# Banks_1_2.net
KiCad netlist of a schematic drawn in Altium Designer
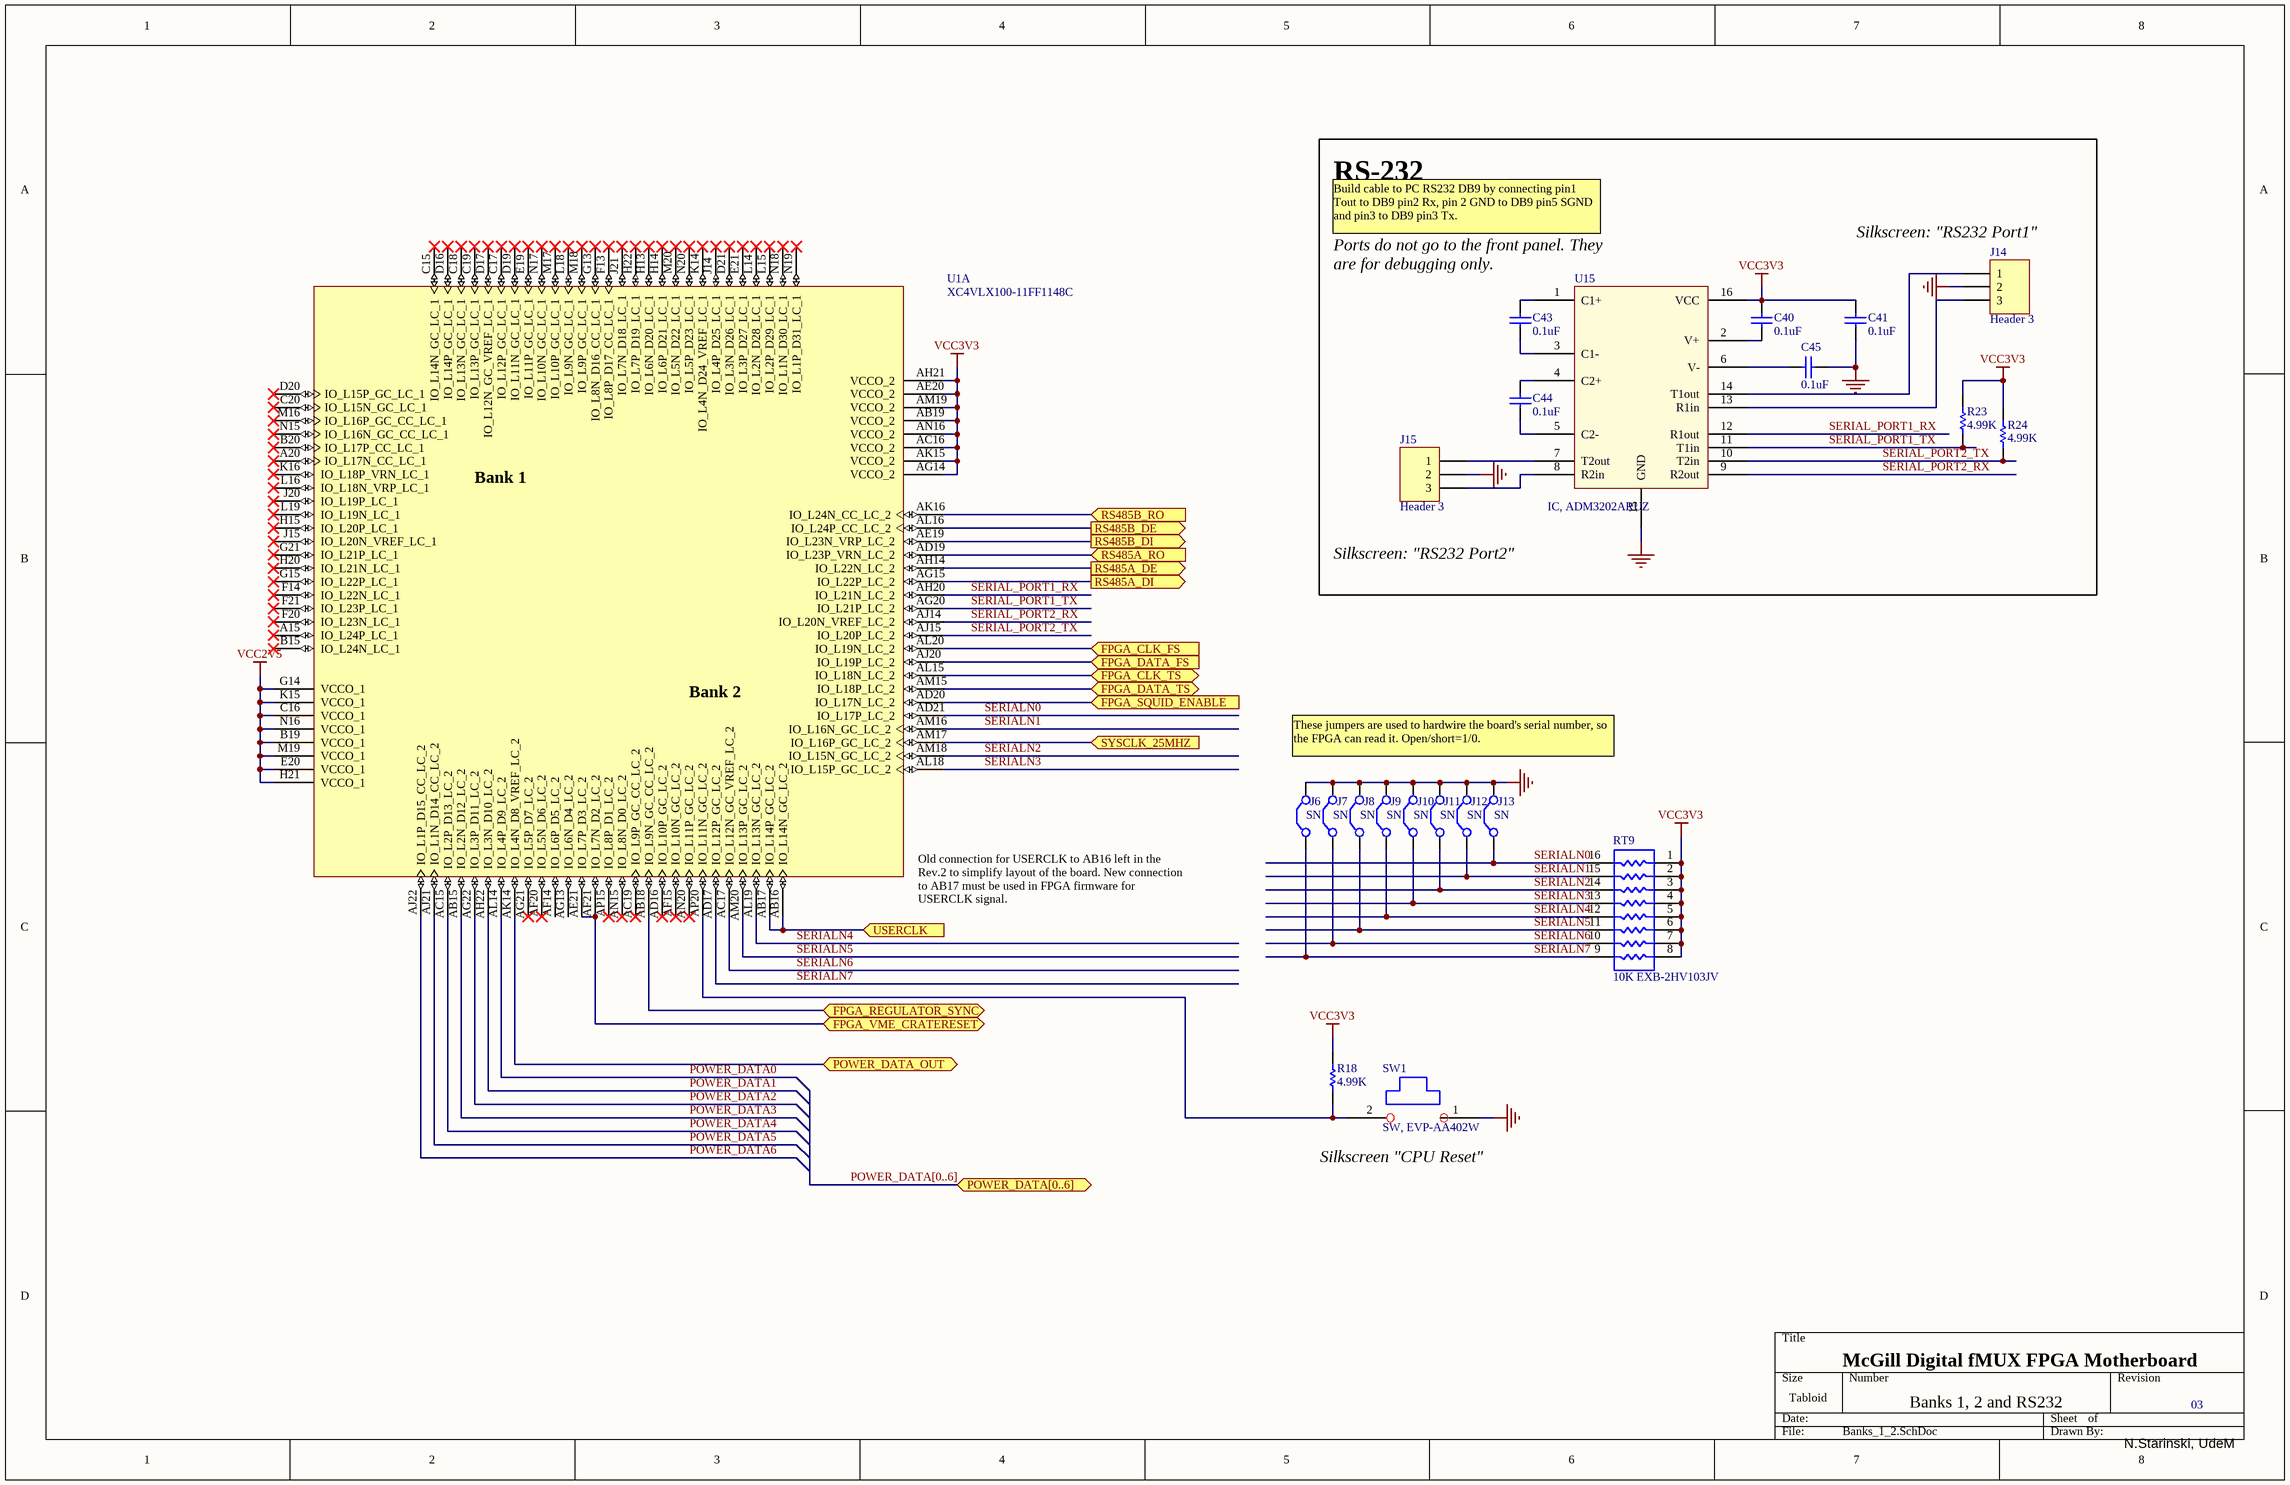
[diagram p0: Banks_1_2.SchDoc]

(export (version "E")
  (design (tool "Eeschema 10.0.6"))
  (components
    (comp (ref "C40")
      (value "0.1uF")
      (footprint "CC1608-0603")
      (description "Capacitor (Semiconductor SIM Model)")
      (fields (field (name "PUBLISHER") "Altium Limited"))
      (libsource (lib "Miscellaneous Devices") (part "Cap Semi"))
    )
    (comp (ref "C41")
      (value "0.1uF")
      (footprint "CC1608-0603")
      (description "Capacitor (Semiconductor SIM Model)")
      (fields (field (name "PUBLISHER") "Altium Limited"))
      (libsource (lib "Miscellaneous Devices") (part "Cap Semi"))
    )
    (comp (ref "C43")
      (value "0.1uF")
      (footprint "CC1608-0603")
      (description "Capacitor (Semiconductor SIM Model)")
      (fields (field (name "PUBLISHER") "Altium Limited"))
      (libsource (lib "Miscellaneous Devices") (part "Cap Semi"))
    )
    (comp (ref "C44")
      (value "0.1uF")
      (footprint "CC1608-0603")
      (description "Capacitor (Semiconductor SIM Model)")
      (fields (field (name "PUBLISHER") "Altium Limited"))
      (libsource (lib "Miscellaneous Devices") (part "Cap Semi"))
    )
    (comp (ref "C45")
      (value "0.1uF")
      (footprint "CC1608-0603")
      (description "Capacitor (Semiconductor SIM Model)")
      (fields (field (name "PUBLISHER") "Altium Limited"))
      (libsource (lib "Miscellaneous Devices") (part "Cap Semi"))
    )
    (comp (ref "J6")
      (value "SN")
      (footprint "MHDR1X2")
      (description "Jumper Wire - Assembly house please short.")
      (fields (field (name "PUBLISHER") "Altium Limited"))
      (libsource (lib "Miscellaneous Devices 02") (part "Jumper"))
    )
    (comp (ref "J7")
      (value "SN")
      (footprint "MHDR1X2")
      (description "Jumper Wire - Assembly house please short.")
      (fields (field (name "PUBLISHER") "Altium Limited"))
      (libsource (lib "Miscellaneous Devices 02") (part "Jumper"))
    )
    (comp (ref "J8")
      (value "SN")
      (footprint "MHDR1X2")
      (description "Jumper Wire - Assembly house please short.")
      (fields (field (name "PUBLISHER") "Altium Limited"))
      (libsource (lib "Miscellaneous Devices 02") (part "Jumper"))
    )
    (comp (ref "J9")
      (value "SN")
      (footprint "MHDR1X2")
      (description "Jumper Wire - Assembly house please short.")
      (fields (field (name "PUBLISHER") "Altium Limited"))
      (libsource (lib "Miscellaneous Devices 02") (part "Jumper"))
    )
    (comp (ref "J10")
      (value "SN")
      (footprint "MHDR1X2")
      (description "Jumper Wire - Assembly house please short.")
      (fields (field (name "PUBLISHER") "Altium Limited"))
      (libsource (lib "Miscellaneous Devices 02") (part "Jumper"))
    )
    (comp (ref "J11")
      (value "SN")
      (footprint "MHDR1X2")
      (description "Jumper Wire - Assembly house please short.")
      (fields (field (name "PUBLISHER") "Altium Limited"))
      (libsource (lib "Miscellaneous Devices 02") (part "Jumper"))
    )
    (comp (ref "J12")
      (value "SN")
      (footprint "MHDR1X2")
      (description "Jumper Wire - Assembly house please short.")
      (fields (field (name "PUBLISHER") "Altium Limited"))
      (libsource (lib "Miscellaneous Devices 02") (part "Jumper"))
    )
    (comp (ref "J13")
      (value "SN")
      (footprint "MHDR1X2")
      (description "Jumper Wire - Assembly house please short.")
      (fields (field (name "PUBLISHER") "Altium Limited"))
      (libsource (lib "Miscellaneous Devices 02") (part "Jumper"))
    )
    (comp (ref "J14")
      (value "Header 3")
      (footprint "HDR1X3")
      (description "Header, 0.1\"  3-Pin straight")
      (fields (field (name "PUBLISHER") "Altium Limited"))
      (libsource (lib "") (part "Header 3_1"))
    )
    (comp (ref "J15")
      (value "Header 3")
      (footprint "HDR1X3")
      (description "Header, 0.1\"  3-Pin straight")
      (fields (field (name "PUBLISHER") "Altium Limited"))
      (libsource (lib "Miscellaneous Connectors") (part "Header 3"))
    )
    (comp (ref "R18")
      (value "4.99K")
      (footprint "CR1608-0603")
      (description "Resistor 0603")
      (fields (field (name "PUBLISHER") "Altium Limited"))
      (libsource (lib "Miscellaneous Devices") (part "Res Semi"))
    )
    (comp (ref "R23")
      (value "4.99K")
      (footprint "CR1608-0603")
      (description "Resistor 0603")
      (fields (field (name "PUBLISHER") "Altium Limited"))
      (libsource (lib "Miscellaneous Devices") (part "Res Semi"))
    )
    (comp (ref "R24")
      (value "4.99K")
      (footprint "CR1608-0603")
      (description "Resistor 0603")
      (fields (field (name "PUBLISHER") "Altium Limited"))
      (libsource (lib "Miscellaneous Devices") (part "Res Semi"))
    )
    (comp (ref "RT9")
      (value "10K EXB-2HV103JV")
      (footprint "0402_Array_2HV")
      (description "Isolated Resistor Network")
      (fields (field (name "PUBLISHER") "Altium Limited"))
      (libsource (lib "Miscellaneous Devices 02") (part "Res Pack3"))
    )
    (comp (ref "SW1")
      (value "SW, EVP-AA402W")
      (footprint "EVPAA")
      (description "Switch, SM pushbutton SPST")
      (libsource (lib "Miscellaneous Devices 02") (part "Tiny Pushbutton Switch"))
    )
    (comp (ref "U1")
      (value "XC4VLX100-11FF1148C")
      (footprint "FF1148")
      (description "Xilinx Virtex-4 LX Platform FPGA, 1148-Ball FFBGA, Speed Grade 11, 768 User I/Os, Commercial Grade")
      (fields (field (name "PUBLISHER") "Altium Limited"))
      (libsource (lib "Xilinx Virtex-4") (part "XC4VLX100-11FF1148C"))
    )
    (comp (ref "U15")
      (value "IC, ADM3202ARUZ")
      (footprint "SSO-G16/X.45")
      (description "Line Drivers/Receivers")
      (libsource (lib "RS_transceivers") (part "ADM3202"))
    )
  )
  (nets
    (net (code "1") (name "/FPGA_CLK_FS") (class "Default")
      (node (ref "U1") (pin "AL20") (pinfunction "IO_L19N_LC_2_AL20") (pintype "bidirectional"))
    )
    (net (code "2") (name "/FPGA_CLK_TS") (class "Default")
      (node (ref "U1") (pin "AL15") (pinfunction "IO_L18N_LC_2_AL15") (pintype "bidirectional"))
    )
    (net (code "3") (name "/FPGA_DATA_FS") (class "Default")
      (node (ref "U1") (pin "AJ20") (pinfunction "IO_L19P_LC_2_AJ20") (pintype "bidirectional"))
    )
    (net (code "4") (name "/FPGA_DATA_TS") (class "Default")
      (node (ref "U1") (pin "AM15") (pinfunction "IO_L18P_LC_2_AM15") (pintype "bidirectional"))
    )
    (net (code "5") (name "/FPGA_REGULATOR_SYNC") (class "Default")
      (node (ref "U1") (pin "AB18") (pinfunction "IO_L9N_GC_CC_LC_2_AB18") (pintype "bidirectional"))
    )
    (net (code "6") (name "/FPGA_SQUID_ENABLE") (class "Default")
      (node (ref "U1") (pin "AD20") (pinfunction "IO_L17N_LC_2_AD20") (pintype "bidirectional"))
    )
    (net (code "7") (name "/FPGA_VME_CRATERESET") (class "Default")
      (node (ref "U1") (pin "AE21") (pinfunction "IO_L7P_D3_LC_2_AE21") (pintype "bidirectional"))
      (node (ref "U1") (pin "AF21") (pinfunction "IO_L7N_D2_LC_2_AF21") (pintype "bidirectional"))
    )
    (net (code "8") (name "/POWER_DATA0") (class "Default")
      (node (ref "U1") (pin "AL14") (pinfunction "IO_L4P_D9_LC_2_AL14") (pintype "bidirectional"))
    )
    (net (code "9") (name "/POWER_DATA1") (class "Default")
      (node (ref "U1") (pin "AH22") (pinfunction "IO_L3N_D10_LC_2_AH22") (pintype "bidirectional"))
    )
    (net (code "10") (name "/POWER_DATA2") (class "Default")
      (node (ref "U1") (pin "AG22") (pinfunction "IO_L3P_D11_LC_2_AG22") (pintype "bidirectional"))
    )
    (net (code "11") (name "/POWER_DATA3") (class "Default")
      (node (ref "U1") (pin "AB15") (pinfunction "IO_L2N_D12_LC_2_AB15") (pintype "bidirectional"))
    )
    (net (code "12") (name "/POWER_DATA4") (class "Default")
      (node (ref "U1") (pin "AC15") (pinfunction "IO_L2P_D13_LC_2_AC15") (pintype "bidirectional"))
    )
    (net (code "13") (name "/POWER_DATA5") (class "Default")
      (node (ref "U1") (pin "AJ21") (pinfunction "IO_L1N_D14_CC_LC_2_AJ21") (pintype "bidirectional"))
    )
    (net (code "14") (name "/POWER_DATA6") (class "Default")
      (node (ref "U1") (pin "AJ22") (pinfunction "IO_L1P_D15_CC_LC_2_AJ22") (pintype "bidirectional"))
    )
    (net (code "16") (name "/POWER_DATA_OUT") (class "Default")
      (node (ref "U1") (pin "AK14") (pinfunction "IO_L4N_D8_VREF_LC_2_AK14") (pintype "bidirectional"))
    )
    (net (code "17") (name "/RS485A_DE") (class "Default")
      (node (ref "U1") (pin "AH14") (pinfunction "IO_L22N_LC_2_AH14") (pintype "bidirectional"))
    )
    (net (code "18") (name "/RS485A_DI") (class "Default")
      (node (ref "U1") (pin "AG15") (pinfunction "IO_L22P_LC_2_AG15") (pintype "bidirectional"))
    )
    (net (code "19") (name "/RS485A_RO") (class "Default")
      (node (ref "U1") (pin "AD19") (pinfunction "IO_L23P_VRN_LC_2_AD19") (pintype "bidirectional"))
    )
    (net (code "20") (name "/RS485B_DE") (class "Default")
      (node (ref "U1") (pin "AL16") (pinfunction "IO_L24P_CC_LC_2_AL16") (pintype "bidirectional"))
    )
    (net (code "21") (name "/RS485B_DI") (class "Default")
      (node (ref "U1") (pin "AE19") (pinfunction "IO_L23N_VRP_LC_2_AE19") (pintype "bidirectional"))
    )
    (net (code "22") (name "/RS485B_RO") (class "Default")
      (node (ref "U1") (pin "AK16") (pinfunction "IO_L24N_CC_LC_2_AK16") (pintype "bidirectional"))
    )
    (net (code "23") (name "/SERIALN0") (class "Default")
      (node (ref "J13") (pin "1") (pinfunction "C1_1") (pintype "passive"))
      (node (ref "RT9") (pin "16") (pinfunction "16_16") (pintype "passive"))
      (node (ref "U1") (pin "AD21") (pinfunction "IO_L17P_LC_2_AD21") (pintype "bidirectional"))
    )
    (net (code "24") (name "/SERIALN1") (class "Default")
      (node (ref "J12") (pin "1") (pinfunction "C1_1") (pintype "passive"))
      (node (ref "RT9") (pin "15") (pinfunction "15_15") (pintype "passive"))
      (node (ref "U1") (pin "AM16") (pinfunction "IO_L16N_GC_LC_2_AM16") (pintype "bidirectional"))
    )
    (net (code "25") (name "/SERIALN2") (class "Default")
      (node (ref "J11") (pin "1") (pinfunction "C1_1") (pintype "passive"))
      (node (ref "RT9") (pin "14") (pinfunction "14_14") (pintype "passive"))
      (node (ref "U1") (pin "AM18") (pinfunction "IO_L15N_GC_LC_2_AM18") (pintype "bidirectional"))
    )
    (net (code "26") (name "/SERIALN3") (class "Default")
      (node (ref "J10") (pin "1") (pinfunction "C1_1") (pintype "passive"))
      (node (ref "RT9") (pin "13") (pinfunction "13_13") (pintype "passive"))
      (node (ref "U1") (pin "AL18") (pinfunction "IO_L15P_GC_LC_2_AL18") (pintype "bidirectional"))
    )
    (net (code "27") (name "/SERIALN4") (class "Default")
      (node (ref "J9") (pin "1") (pinfunction "C1_1") (pintype "passive"))
      (node (ref "RT9") (pin "12") (pinfunction "12_12") (pintype "passive"))
      (node (ref "U1") (pin "AL19") (pinfunction "IO_L13N_GC_LC_2_AL19") (pintype "bidirectional"))
    )
    (net (code "28") (name "/SERIALN5") (class "Default")
      (node (ref "J8") (pin "1") (pinfunction "C1_1") (pintype "passive"))
      (node (ref "RT9") (pin "11") (pinfunction "11_11") (pintype "passive"))
      (node (ref "U1") (pin "AM20") (pinfunction "IO_L13P_GC_LC_2_AM20") (pintype "bidirectional"))
    )
    (net (code "29") (name "/SERIALN6") (class "Default")
      (node (ref "J7") (pin "1") (pinfunction "C1_1") (pintype "passive"))
      (node (ref "RT9") (pin "10") (pinfunction "10_10") (pintype "passive"))
      (node (ref "U1") (pin "AC17") (pinfunction "IO_L12N_GC_VREF_LC_2_AC17") (pintype "bidirectional"))
    )
    (net (code "30") (name "/SERIALN7") (class "Default")
      (node (ref "J6") (pin "1") (pinfunction "C1_1") (pintype "passive"))
      (node (ref "RT9") (pin "9") (pinfunction "9_9") (pintype "passive"))
      (node (ref "U1") (pin "AD17") (pinfunction "IO_L12P_GC_LC_2_AD17") (pintype "bidirectional"))
    )
    (net (code "31") (name "/SERIAL_PORT1_RX") (class "Default")
      (node (ref "U1") (pin "AH20") (pinfunction "IO_L21N_LC_2_AH20") (pintype "bidirectional"))
      (node (ref "U15") (pin "12") (pinfunction "R1out_12") (pintype "passive"))
    )
    (net (code "32") (name "/SERIAL_PORT1_TX") (class "Default")
      (node (ref "R23") (pin "1") (pinfunction "1_1") (pintype "passive"))
      (node (ref "U1") (pin "AG20") (pinfunction "IO_L21P_LC_2_AG20") (pintype "bidirectional"))
      (node (ref "U15") (pin "11") (pinfunction "T1in_11") (pintype "passive"))
    )
    (net (code "33") (name "/SERIAL_PORT2_RX") (class "Default")
      (node (ref "U1") (pin "AJ14") (pinfunction "IO_L20N_VREF_LC_2_AJ14") (pintype "bidirectional"))
      (node (ref "U15") (pin "9") (pinfunction "R2out_9") (pintype "passive"))
    )
    (net (code "34") (name "/SERIAL_PORT2_TX") (class "Default")
      (node (ref "R24") (pin "1") (pinfunction "1_1") (pintype "passive"))
      (node (ref "U1") (pin "AJ15") (pinfunction "IO_L20P_LC_2_AJ15") (pintype "bidirectional"))
      (node (ref "U15") (pin "10") (pinfunction "T2in_10") (pintype "passive"))
    )
    (net (code "35") (name "/SYSCLK_25MHZ") (class "Default")
      (node (ref "U1") (pin "AM17") (pinfunction "IO_L16P_GC_LC_2_AM17") (pintype "bidirectional"))
    )
    (net (code "36") (name "/USERCLK") (class "Default")
      (node (ref "U1") (pin "AB16") (pinfunction "IO_L14N_GC_LC_2_AB16") (pintype "bidirectional"))
      (node (ref "U1") (pin "AB17") (pinfunction "IO_L14P_GC_LC_2_AB17") (pintype "bidirectional"))
    )
    (net (code "37") (name "GND") (class "Default")
      (node (ref "C41") (pin "1") (pinfunction "1_1") (pintype "passive"))
      (node (ref "C45") (pin "2") (pinfunction "2_2") (pintype "passive"))
      (node (ref "J10") (pin "2") (pinfunction "C2_2") (pintype "passive"))
      (node (ref "J11") (pin "2") (pinfunction "C2_2") (pintype "passive"))
      (node (ref "J12") (pin "2") (pinfunction "C2_2") (pintype "passive"))
      (node (ref "J13") (pin "2") (pinfunction "C2_2") (pintype "passive"))
      (node (ref "J14") (pin "2") (pinfunction "2_2") (pintype "passive"))
      (node (ref "J15") (pin "2") (pinfunction "2_2") (pintype "passive"))
      (node (ref "J6") (pin "2") (pinfunction "C2_2") (pintype "passive"))
      (node (ref "J7") (pin "2") (pinfunction "C2_2") (pintype "passive"))
      (node (ref "J8") (pin "2") (pinfunction "C2_2") (pintype "passive"))
      (node (ref "J9") (pin "2") (pinfunction "C2_2") (pintype "passive"))
      (node (ref "SW1") (pin "1") (pinfunction "1_1") (pintype "passive"))
      (node (ref "U15") (pin "15") (pinfunction "GND_15") (pintype "power_in"))
    )
    (net (code "38") (name "Net-(U1A-IO_L11N_GC_LC_2)") (class "Default")
      (node (ref "R18") (pin "1") (pinfunction "1_1") (pintype "passive"))
      (node (ref "SW1") (pin "2") (pinfunction "2_2") (pintype "passive"))
      (node (ref "U1") (pin "AP20") (pinfunction "IO_L11N_GC_LC_2_AP20") (pintype "bidirectional"))
    )
    (net (code "39") (name "Net-(U15-C1+)") (class "Default")
      (node (ref "C43") (pin "2") (pinfunction "2_2") (pintype "passive"))
      (node (ref "U15") (pin "1") (pinfunction "C1+_1") (pintype "passive"))
    )
    (net (code "40") (name "Net-(U15-C1-)") (class "Default")
      (node (ref "C43") (pin "1") (pinfunction "1_1") (pintype "passive"))
      (node (ref "U15") (pin "3") (pinfunction "C1-_3") (pintype "passive"))
    )
    (net (code "41") (name "Net-(U15-C2+)") (class "Default")
      (node (ref "C44") (pin "2") (pinfunction "2_2") (pintype "passive"))
      (node (ref "U15") (pin "4") (pinfunction "C2+_4") (pintype "passive"))
    )
    (net (code "42") (name "Net-(U15-C2-)") (class "Default")
      (node (ref "C44") (pin "1") (pinfunction "1_1") (pintype "passive"))
      (node (ref "U15") (pin "5") (pinfunction "C2-_5") (pintype "passive"))
    )
    (net (code "43") (name "Net-(U15-R1in)") (class "Default")
      (node (ref "J14") (pin "3") (pinfunction "3_3") (pintype "passive"))
      (node (ref "U15") (pin "13") (pinfunction "R1in_13") (pintype "passive"))
    )
    (net (code "44") (name "Net-(U15-R2in)") (class "Default")
      (node (ref "J15") (pin "3") (pinfunction "3_3") (pintype "passive"))
      (node (ref "U15") (pin "8") (pinfunction "R2in_8") (pintype "passive"))
    )
    (net (code "45") (name "Net-(U15-T1out)") (class "Default")
      (node (ref "J14") (pin "1") (pinfunction "1_1") (pintype "passive"))
      (node (ref "U15") (pin "14") (pinfunction "T1out_14") (pintype "passive"))
    )
    (net (code "46") (name "Net-(U15-T2out)") (class "Default")
      (node (ref "J15") (pin "1") (pinfunction "1_1") (pintype "passive"))
      (node (ref "U15") (pin "7") (pinfunction "T2out_7") (pintype "passive"))
    )
    (net (code "47") (name "Net-(U15-V+)") (class "Default")
      (node (ref "C40") (pin "1") (pinfunction "1_1") (pintype "passive"))
      (node (ref "U15") (pin "2") (pinfunction "V+_2") (pintype "power_in"))
    )
    (net (code "48") (name "Net-(U15-V-)") (class "Default")
      (node (ref "C45") (pin "1") (pinfunction "1_1") (pintype "passive"))
      (node (ref "U15") (pin "6") (pinfunction "V-_6") (pintype "power_in"))
    )
    (net (code "49") (name "VCC2V5") (class "Default")
      (node (ref "U1") (pin "B19") (pinfunction "VCCO_1_B19") (pintype "power_in"))
      (node (ref "U1") (pin "C16") (pinfunction "VCCO_1_C16") (pintype "power_in"))
      (node (ref "U1") (pin "E20") (pinfunction "VCCO_1_E20") (pintype "power_in"))
      (node (ref "U1") (pin "G14") (pinfunction "VCCO_1_G14") (pintype "power_in"))
      (node (ref "U1") (pin "H21") (pinfunction "VCCO_1_H21") (pintype "power_in"))
      (node (ref "U1") (pin "K15") (pinfunction "VCCO_1_K15") (pintype "power_in"))
      (node (ref "U1") (pin "M19") (pinfunction "VCCO_1_M19") (pintype "power_in"))
      (node (ref "U1") (pin "N16") (pinfunction "VCCO_1_N16") (pintype "power_in"))
    )
    (net (code "50") (name "VCC3V3") (class "Default")
      (node (ref "C40") (pin "2") (pinfunction "2_2") (pintype "passive"))
      (node (ref "C41") (pin "2") (pinfunction "2_2") (pintype "passive"))
      (node (ref "R18") (pin "2") (pinfunction "2_2") (pintype "passive"))
      (node (ref "R23") (pin "2") (pinfunction "2_2") (pintype "passive"))
      (node (ref "R24") (pin "2") (pinfunction "2_2") (pintype "passive"))
      (node (ref "RT9") (pin "1") (pinfunction "1_1") (pintype "passive"))
      (node (ref "RT9") (pin "2") (pinfunction "2_2") (pintype "passive"))
      (node (ref "RT9") (pin "3") (pinfunction "3_3") (pintype "passive"))
      (node (ref "RT9") (pin "4") (pinfunction "4_4") (pintype "passive"))
      (node (ref "RT9") (pin "5") (pinfunction "5_5") (pintype "passive"))
      (node (ref "RT9") (pin "6") (pinfunction "6_6") (pintype "passive"))
      (node (ref "RT9") (pin "7") (pinfunction "7_7") (pintype "passive"))
      (node (ref "RT9") (pin "8") (pinfunction "8_8") (pintype "passive"))
      (node (ref "U1") (pin "AB19") (pinfunction "VCCO_2_AB19") (pintype "power_in"))
      (node (ref "U1") (pin "AC16") (pinfunction "VCCO_2_AC16") (pintype "power_in"))
      (node (ref "U1") (pin "AE20") (pinfunction "VCCO_2_AE20") (pintype "power_in"))
      (node (ref "U1") (pin "AG14") (pinfunction "VCCO_2_AG14") (pintype "power_in"))
      (node (ref "U1") (pin "AH21") (pinfunction "VCCO_2_AH21") (pintype "power_in"))
      (node (ref "U1") (pin "AK15") (pinfunction "VCCO_2_AK15") (pintype "power_in"))
      (node (ref "U1") (pin "AM19") (pinfunction "VCCO_2_AM19") (pintype "power_in"))
      (node (ref "U1") (pin "AN16") (pinfunction "VCCO_2_AN16") (pintype "power_in"))
      (node (ref "U15") (pin "16") (pinfunction "VCC_16") (pintype "power_in"))
    )
    (net (code "51") (name "unconnected-(U1A-IO_L1N_D30_LC_1-PadN18)") (class "Default")
      (node (ref "U1") (pin "N18") (pinfunction "IO_L1N_D30_LC_1_N18") (pintype "bidirectional+no_connect"))
    )
    (net (code "52") (name "unconnected-(U1A-IO_L1P_D31_LC_1-PadN19)") (class "Default")
      (node (ref "U1") (pin "N19") (pinfunction "IO_L1P_D31_LC_1_N19") (pintype "bidirectional+no_connect"))
    )
    (net (code "53") (name "unconnected-(U1A-IO_L2N_D28_LC_1-PadL14)") (class "Default")
      (node (ref "U1") (pin "L14") (pinfunction "IO_L2N_D28_LC_1_L14") (pintype "bidirectional+no_connect"))
    )
    (net (code "54") (name "unconnected-(U1A-IO_L2P_D29_LC_1-PadL15)") (class "Default")
      (node (ref "U1") (pin "L15") (pinfunction "IO_L2P_D29_LC_1_L15") (pintype "bidirectional+no_connect"))
    )
    (net (code "55") (name "unconnected-(U1A-IO_L3N_D26_LC_1-PadD21)") (class "Default")
      (node (ref "U1") (pin "D21") (pinfunction "IO_L3N_D26_LC_1_D21") (pintype "bidirectional+no_connect"))
    )
    (net (code "56") (name "unconnected-(U1A-IO_L3P_D27_LC_1-PadE21)") (class "Default")
      (node (ref "U1") (pin "E21") (pinfunction "IO_L3P_D27_LC_1_E21") (pintype "bidirectional+no_connect"))
    )
    (net (code "57") (name "unconnected-(U1A-IO_L4N_D24_VREF_LC_1-PadK14)") (class "Default")
      (node (ref "U1") (pin "K14") (pinfunction "IO_L4N_D24_VREF_LC_1_K14") (pintype "bidirectional+no_connect"))
    )
    (net (code "58") (name "unconnected-(U1A-IO_L4P_D25_LC_1-PadJ14)") (class "Default")
      (node (ref "U1") (pin "J14") (pinfunction "IO_L4P_D25_LC_1_J14") (pintype "bidirectional+no_connect"))
    )
    (net (code "59") (name "unconnected-(U1A-IO_L5N_D6_LC_2-PadAF20)") (class "Default")
      (node (ref "U1") (pin "AF20") (pinfunction "IO_L5N_D6_LC_2_AF20") (pintype "bidirectional+no_connect"))
    )
    (net (code "60") (name "unconnected-(U1A-IO_L5N_D22_LC_1-PadM20)") (class "Default")
      (node (ref "U1") (pin "M20") (pinfunction "IO_L5N_D22_LC_1_M20") (pintype "bidirectional+no_connect"))
    )
    (net (code "61") (name "unconnected-(U1A-IO_L5P_D7_LC_2-PadAG21)") (class "Default")
      (node (ref "U1") (pin "AG21") (pinfunction "IO_L5P_D7_LC_2_AG21") (pintype "bidirectional+no_connect"))
    )
    (net (code "62") (name "unconnected-(U1A-IO_L5P_D23_LC_1-PadN20)") (class "Default")
      (node (ref "U1") (pin "N20") (pinfunction "IO_L5P_D23_LC_1_N20") (pintype "bidirectional+no_connect"))
    )
    (net (code "63") (name "unconnected-(U1A-IO_L6N_D4_LC_2-PadAG13)") (class "Default")
      (node (ref "U1") (pin "AG13") (pinfunction "IO_L6N_D4_LC_2_AG13") (pintype "bidirectional"))
    )
    (net (code "64") (name "unconnected-(U1A-IO_L6N_D20_LC_1-PadH13)") (class "Default")
      (node (ref "U1") (pin "H13") (pinfunction "IO_L6N_D20_LC_1_H13") (pintype "bidirectional+no_connect"))
    )
    (net (code "65") (name "unconnected-(U1A-IO_L6P_D5_LC_2-PadAF14)") (class "Default")
      (node (ref "U1") (pin "AF14") (pinfunction "IO_L6P_D5_LC_2_AF14") (pintype "bidirectional"))
    )
    (net (code "66") (name "unconnected-(U1A-IO_L6P_D21_LC_1-PadH14)") (class "Default")
      (node (ref "U1") (pin "H14") (pinfunction "IO_L6P_D21_LC_1_H14") (pintype "bidirectional+no_connect"))
    )
    (net (code "67") (name "unconnected-(U1A-IO_L7N_D18_LC_1-PadJ21)") (class "Default")
      (node (ref "U1") (pin "J21") (pinfunction "IO_L7N_D18_LC_1_J21") (pintype "bidirectional+no_connect"))
    )
    (net (code "68") (name "unconnected-(U1A-IO_L7P_D19_LC_1-PadH22)") (class "Default")
      (node (ref "U1") (pin "H22") (pinfunction "IO_L7P_D19_LC_1_H22") (pintype "bidirectional+no_connect"))
    )
    (net (code "69") (name "unconnected-(U1A-IO_L8N_D0_LC_2-PadAN15)") (class "Default")
      (node (ref "U1") (pin "AN15") (pinfunction "IO_L8N_D0_LC_2_AN15") (pintype "bidirectional+no_connect"))
    )
    (net (code "70") (name "unconnected-(U1A-IO_L8N_D16_CC_LC_1-PadG13)") (class "Default")
      (node (ref "U1") (pin "G13") (pinfunction "IO_L8N_D16_CC_LC_1_G13") (pintype "bidirectional+no_connect"))
    )
    (net (code "71") (name "unconnected-(U1A-IO_L8P_D1_LC_2-PadAP15)") (class "Default")
      (node (ref "U1") (pin "AP15") (pinfunction "IO_L8P_D1_LC_2_AP15") (pintype "bidirectional+no_connect"))
    )
    (net (code "72") (name "unconnected-(U1A-IO_L8P_D17_CC_LC_1-PadF13)") (class "Default")
      (node (ref "U1") (pin "F13") (pinfunction "IO_L8P_D17_CC_LC_1_F13") (pintype "bidirectional+no_connect"))
    )
    (net (code "73") (name "unconnected-(U1A-IO_L9N_GC_LC_1-PadL18)") (class "Default")
      (node (ref "U1") (pin "L18") (pinfunction "IO_L9N_GC_LC_1_L18") (pintype "bidirectional+no_connect"))
    )
    (net (code "74") (name "unconnected-(U1A-IO_L9P_GC_CC_LC_2-PadAC19)") (class "Default")
      (node (ref "U1") (pin "AC19") (pinfunction "IO_L9P_GC_CC_LC_2_AC19") (pintype "bidirectional+no_connect"))
    )
    (net (code "75") (name "unconnected-(U1A-IO_L9P_GC_LC_1-PadM18)") (class "Default")
      (node (ref "U1") (pin "M18") (pinfunction "IO_L9P_GC_LC_1_M18") (pintype "bidirectional+no_connect"))
    )
    (net (code "76") (name "unconnected-(U1A-IO_L10N_GC_LC_1-PadN17)") (class "Default")
      (node (ref "U1") (pin "N17") (pinfunction "IO_L10N_GC_LC_1_N17") (pintype "bidirectional+no_connect"))
    )
    (net (code "77") (name "unconnected-(U1A-IO_L10N_GC_LC_2-PadAF15)") (class "Default")
      (node (ref "U1") (pin "AF15") (pinfunction "IO_L10N_GC_LC_2_AF15") (pintype "bidirectional+no_connect"))
    )
    (net (code "78") (name "unconnected-(U1A-IO_L10P_GC_LC_1-PadM17)") (class "Default")
      (node (ref "U1") (pin "M17") (pinfunction "IO_L10P_GC_LC_1_M17") (pintype "bidirectional+no_connect"))
    )
    (net (code "79") (name "unconnected-(U1A-IO_L10P_GC_LC_2-PadAD16)") (class "Default")
      (node (ref "U1") (pin "AD16") (pinfunction "IO_L10P_GC_LC_2_AD16") (pintype "bidirectional+no_connect"))
    )
    (net (code "80") (name "unconnected-(U1A-IO_L11N_GC_LC_1-PadD19)") (class "Default")
      (node (ref "U1") (pin "D19") (pinfunction "IO_L11N_GC_LC_1_D19") (pintype "bidirectional+no_connect"))
    )
    (net (code "81") (name "unconnected-(U1A-IO_L11P_GC_LC_1-PadE19)") (class "Default")
      (node (ref "U1") (pin "E19") (pinfunction "IO_L11P_GC_LC_1_E19") (pintype "bidirectional+no_connect"))
    )
    (net (code "82") (name "unconnected-(U1A-IO_L11P_GC_LC_2-PadAN20)") (class "Default")
      (node (ref "U1") (pin "AN20") (pinfunction "IO_L11P_GC_LC_2_AN20") (pintype "bidirectional+no_connect"))
    )
    (net (code "83") (name "unconnected-(U1A-IO_L12N_GC_VREF_LC_1-PadD17)") (class "Default")
      (node (ref "U1") (pin "D17") (pinfunction "IO_L12N_GC_VREF_LC_1_D17") (pintype "bidirectional+no_connect"))
    )
    (net (code "84") (name "unconnected-(U1A-IO_L12P_GC_LC_1-PadC17)") (class "Default")
      (node (ref "U1") (pin "C17") (pinfunction "IO_L12P_GC_LC_1_C17") (pintype "bidirectional+no_connect"))
    )
    (net (code "85") (name "unconnected-(U1A-IO_L13N_GC_LC_1-PadC18)") (class "Default")
      (node (ref "U1") (pin "C18") (pinfunction "IO_L13N_GC_LC_1_C18") (pintype "bidirectional+no_connect"))
    )
    (net (code "86") (name "unconnected-(U1A-IO_L13P_GC_LC_1-PadC19)") (class "Default")
      (node (ref "U1") (pin "C19") (pinfunction "IO_L13P_GC_LC_1_C19") (pintype "bidirectional+no_connect"))
    )
    (net (code "87") (name "unconnected-(U1A-IO_L14N_GC_LC_1-PadC15)") (class "Default")
      (node (ref "U1") (pin "C15") (pinfunction "IO_L14N_GC_LC_1_C15") (pintype "bidirectional+no_connect"))
    )
    (net (code "88") (name "unconnected-(U1A-IO_L14P_GC_LC_1-PadD16)") (class "Default")
      (node (ref "U1") (pin "D16") (pinfunction "IO_L14P_GC_LC_1_D16") (pintype "bidirectional+no_connect"))
    )
    (net (code "89") (name "unconnected-(U1A-IO_L15N_GC_LC_1-PadC20)") (class "Default")
      (node (ref "U1") (pin "C20") (pinfunction "IO_L15N_GC_LC_1_C20") (pintype "bidirectional+no_connect"))
    )
    (net (code "90") (name "unconnected-(U1A-IO_L15P_GC_LC_1-PadD20)") (class "Default")
      (node (ref "U1") (pin "D20") (pinfunction "IO_L15P_GC_LC_1_D20") (pintype "bidirectional+no_connect"))
    )
    (net (code "91") (name "unconnected-(U1A-IO_L16N_GC_CC_LC_1-PadN15)") (class "Default")
      (node (ref "U1") (pin "N15") (pinfunction "IO_L16N_GC_CC_LC_1_N15") (pintype "bidirectional+no_connect"))
    )
    (net (code "92") (name "unconnected-(U1A-IO_L16P_GC_CC_LC_1-PadM16)") (class "Default")
      (node (ref "U1") (pin "M16") (pinfunction "IO_L16P_GC_CC_LC_1_M16") (pintype "bidirectional+no_connect"))
    )
    (net (code "93") (name "unconnected-(U1A-IO_L17N_CC_LC_1-PadA20)") (class "Default")
      (node (ref "U1") (pin "A20") (pinfunction "IO_L17N_CC_LC_1_A20") (pintype "bidirectional+no_connect"))
    )
    (net (code "94") (name "unconnected-(U1A-IO_L17P_CC_LC_1-PadB20)") (class "Default")
      (node (ref "U1") (pin "B20") (pinfunction "IO_L17P_CC_LC_1_B20") (pintype "bidirectional+no_connect"))
    )
    (net (code "95") (name "unconnected-(U1A-IO_L18N_VRP_LC_1-PadL16)") (class "Default")
      (node (ref "U1") (pin "L16") (pinfunction "IO_L18N_VRP_LC_1_L16") (pintype "bidirectional+no_connect"))
    )
    (net (code "96") (name "unconnected-(U1A-IO_L18P_VRN_LC_1-PadK16)") (class "Default")
      (node (ref "U1") (pin "K16") (pinfunction "IO_L18P_VRN_LC_1_K16") (pintype "bidirectional+no_connect"))
    )
    (net (code "97") (name "unconnected-(U1A-IO_L19N_LC_1-PadL19)") (class "Default")
      (node (ref "U1") (pin "L19") (pinfunction "IO_L19N_LC_1_L19") (pintype "bidirectional+no_connect"))
    )
    (net (code "98") (name "unconnected-(U1A-IO_L19P_LC_1-PadJ20)") (class "Default")
      (node (ref "U1") (pin "J20") (pinfunction "IO_L19P_LC_1_J20") (pintype "bidirectional+no_connect"))
    )
    (net (code "99") (name "unconnected-(U1A-IO_L20N_VREF_LC_1-PadJ15)") (class "Default")
      (node (ref "U1") (pin "J15") (pinfunction "IO_L20N_VREF_LC_1_J15") (pintype "bidirectional+no_connect"))
    )
    (net (code "100") (name "unconnected-(U1A-IO_L20P_LC_1-PadH15)") (class "Default")
      (node (ref "U1") (pin "H15") (pinfunction "IO_L20P_LC_1_H15") (pintype "bidirectional+no_connect"))
    )
    (net (code "101") (name "unconnected-(U1A-IO_L21N_LC_1-PadH20)") (class "Default")
      (node (ref "U1") (pin "H20") (pinfunction "IO_L21N_LC_1_H20") (pintype "bidirectional+no_connect"))
    )
    (net (code "102") (name "unconnected-(U1A-IO_L21P_LC_1-PadG21)") (class "Default")
      (node (ref "U1") (pin "G21") (pinfunction "IO_L21P_LC_1_G21") (pintype "bidirectional+no_connect"))
    )
    (net (code "103") (name "unconnected-(U1A-IO_L22N_LC_1-PadF14)") (class "Default")
      (node (ref "U1") (pin "F14") (pinfunction "IO_L22N_LC_1_F14") (pintype "bidirectional+no_connect"))
    )
    (net (code "104") (name "unconnected-(U1A-IO_L22P_LC_1-PadG15)") (class "Default")
      (node (ref "U1") (pin "G15") (pinfunction "IO_L22P_LC_1_G15") (pintype "bidirectional+no_connect"))
    )
    (net (code "105") (name "unconnected-(U1A-IO_L23N_LC_1-PadF20)") (class "Default")
      (node (ref "U1") (pin "F20") (pinfunction "IO_L23N_LC_1_F20") (pintype "bidirectional+no_connect"))
    )
    (net (code "106") (name "unconnected-(U1A-IO_L23P_LC_1-PadF21)") (class "Default")
      (node (ref "U1") (pin "F21") (pinfunction "IO_L23P_LC_1_F21") (pintype "bidirectional+no_connect"))
    )
    (net (code "107") (name "unconnected-(U1A-IO_L24N_LC_1-PadB15)") (class "Default")
      (node (ref "U1") (pin "B15") (pinfunction "IO_L24N_LC_1_B15") (pintype "bidirectional+no_connect"))
    )
    (net (code "108") (name "unconnected-(U1A-IO_L24P_LC_1-PadA15)") (class "Default")
      (node (ref "U1") (pin "A15") (pinfunction "IO_L24P_LC_1_A15") (pintype "bidirectional+no_connect"))
    )
  )
)
